# AudioMega_v102.net
KiCad netlist of a schematic drawn in EAGLE
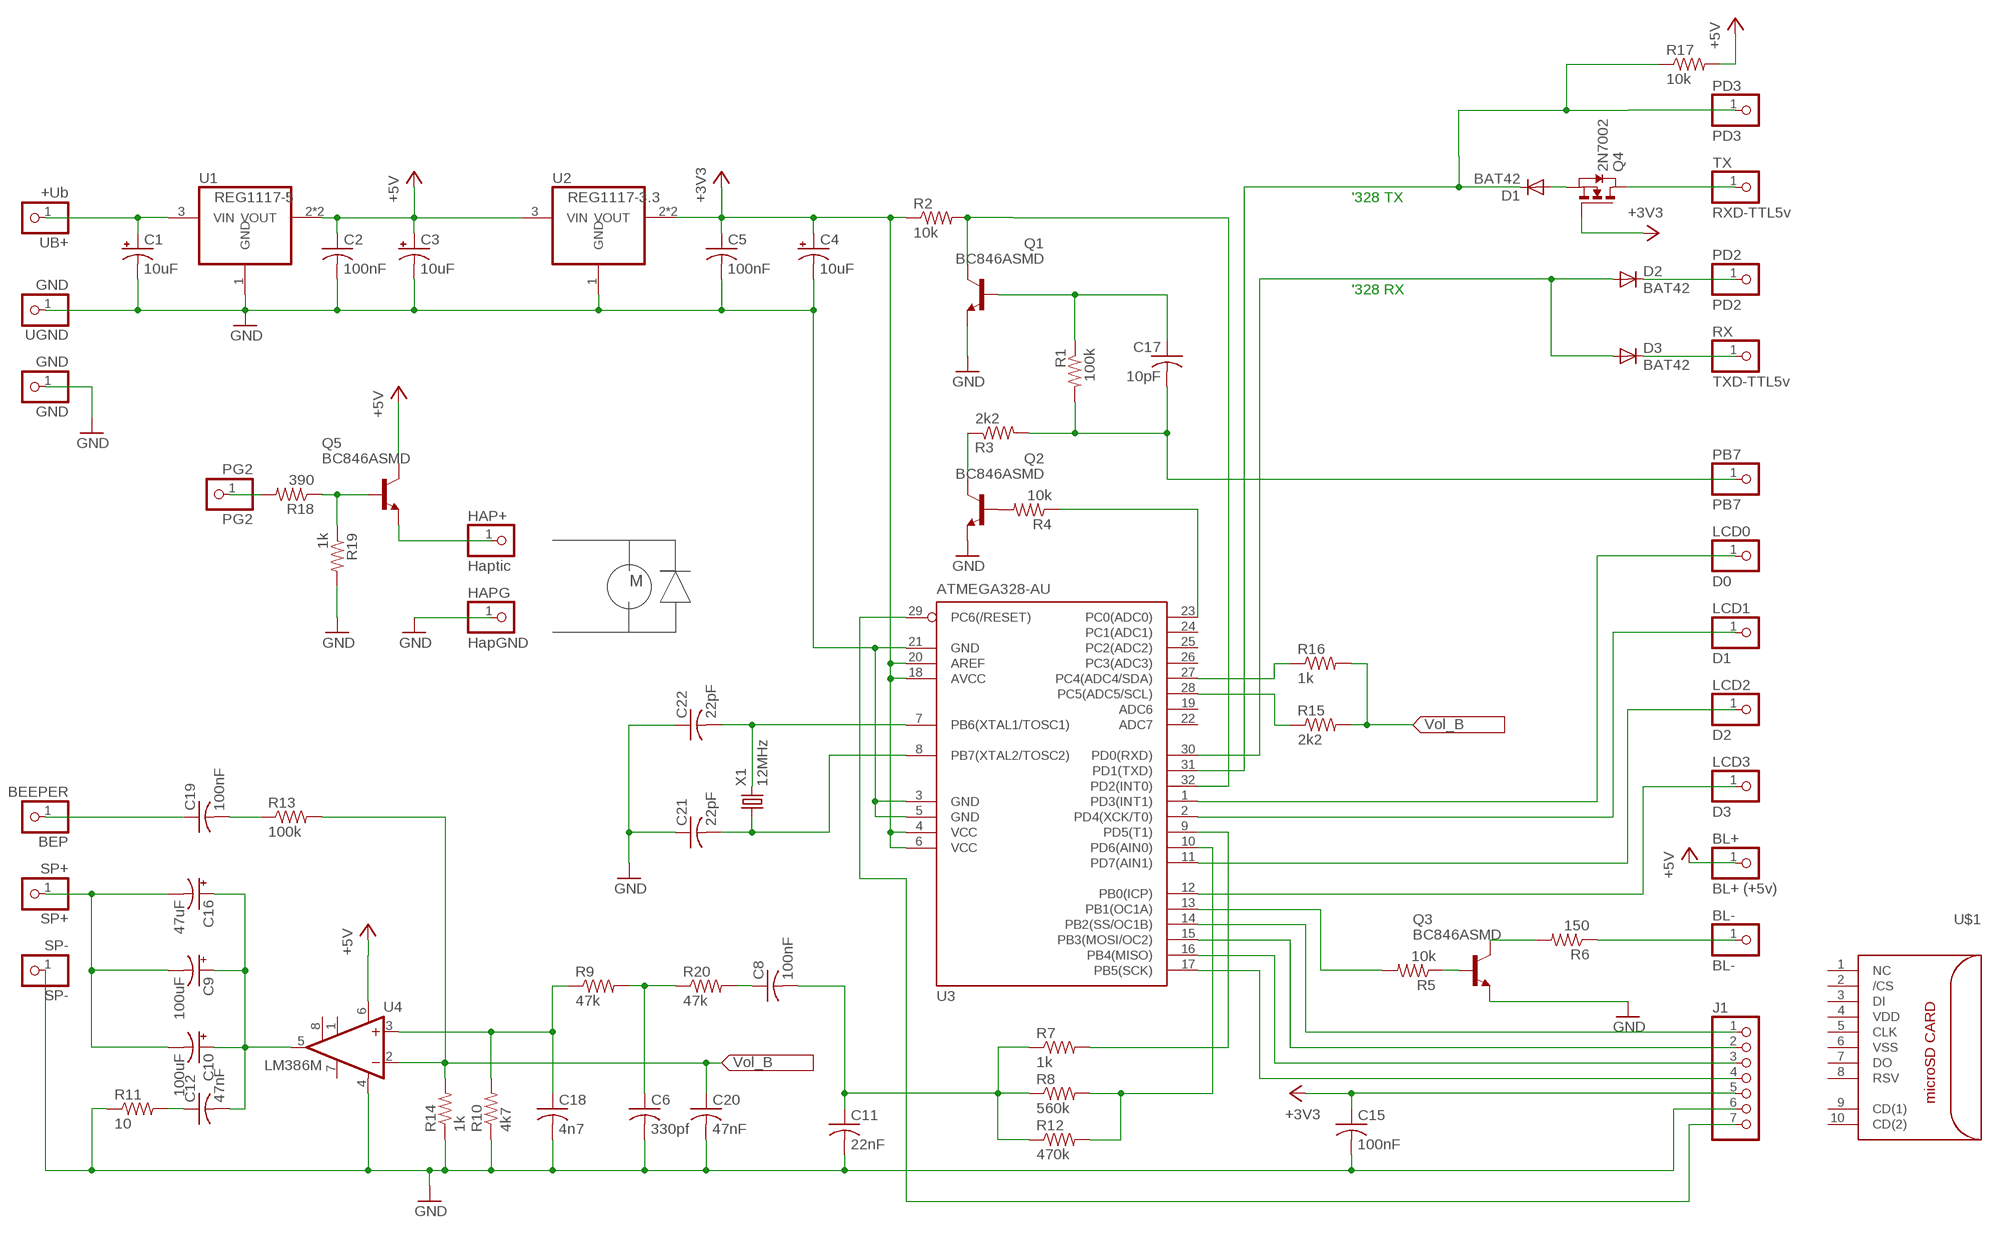
[diagram p0: schematic, sheet 1]

(export (version "E")
  (design (tool "Eeschema 10.0.6"))
  (components
    (comp (ref "BEP")
      (value "BEEPER")
      (footprint "eagle-import:1X01")
      (libsource (lib "eagle-import") (part "PINHD-1X1"))
    )
    (comp (ref "BL+")
      (value "BL+ (+5v)")
      (footprint "eagle-import:1X01")
      (libsource (lib "eagle-import") (part "PINHD-1X1"))
    )
    (comp (ref "BL-")
      (value "BL-")
      (footprint "eagle-import:1X01")
      (libsource (lib "eagle-import") (part "PINHD-1X1"))
    )
    (comp (ref "C1")
      (value "10uF")
      (footprint "eagle-import:CT3528")
      (libsource (lib "eagle-import") (part "CPOL-USCT3528"))
    )
    (comp (ref "C2")
      (value "100nF")
      (footprint "eagle-import:C1206")
      (libsource (lib "eagle-import") (part "C-USC1206"))
    )
    (comp (ref "C3")
      (value "10uF")
      (footprint "eagle-import:CT3528")
      (libsource (lib "eagle-import") (part "CPOL-USCT3528"))
    )
    (comp (ref "C4")
      (value "10uF")
      (footprint "eagle-import:CT3528")
      (libsource (lib "eagle-import") (part "CPOL-USCT3528"))
    )
    (comp (ref "C5")
      (value "100nF")
      (footprint "eagle-import:C1206")
      (libsource (lib "eagle-import") (part "C-USC1206"))
    )
    (comp (ref "C6")
      (value "330pf")
      (footprint "eagle-import:C1206")
      (libsource (lib "eagle-import") (part "C-USC1206"))
    )
    (comp (ref "C8")
      (value "100nF")
      (footprint "eagle-import:C1206")
      (libsource (lib "eagle-import") (part "C-USC1206"))
    )
    (comp (ref "C9")
      (value "100uF")
      (footprint "eagle-import:CT6032")
      (libsource (lib "eagle-import") (part "CPOL-USCT6032"))
    )
    (comp (ref "C10")
      (value "100uF")
      (footprint "eagle-import:CT6032")
      (libsource (lib "eagle-import") (part "CPOL-USCT6032"))
    )
    (comp (ref "C11")
      (value "22nF")
      (footprint "eagle-import:C1206")
      (libsource (lib "eagle-import") (part "C-USC1206"))
    )
    (comp (ref "C12")
      (value "47nF")
      (footprint "eagle-import:C1206")
      (libsource (lib "eagle-import") (part "C-USC1206"))
    )
    (comp (ref "C15")
      (value "100nF")
      (footprint "eagle-import:C1206")
      (libsource (lib "eagle-import") (part "C-USC1206"))
    )
    (comp (ref "C16")
      (value "47uF")
      (footprint "eagle-import:CT6032")
      (libsource (lib "eagle-import") (part "CPOL-USCT6032"))
    )
    (comp (ref "C17")
      (value "10pF")
      (footprint "eagle-import:C1206")
      (libsource (lib "eagle-import") (part "C-USC1206"))
    )
    (comp (ref "C18")
      (value "4n7")
      (footprint "eagle-import:C1206")
      (libsource (lib "eagle-import") (part "C-USC1206"))
    )
    (comp (ref "C19")
      (value "100nF")
      (footprint "eagle-import:C1206")
      (libsource (lib "eagle-import") (part "C-USC1206"))
    )
    (comp (ref "C20")
      (value "47nF")
      (footprint "eagle-import:C1206")
      (libsource (lib "eagle-import") (part "C-USC1206"))
    )
    (comp (ref "C21")
      (value "22pF")
      (footprint "eagle-import:C1206")
      (libsource (lib "eagle-import") (part "C-USC1206"))
    )
    (comp (ref "C22")
      (value "22pF")
      (footprint "eagle-import:C1206")
      (libsource (lib "eagle-import") (part "C-USC1206"))
    )
    (comp (ref "D1")
      (value "BAT42")
      (footprint "eagle-import:SOD123")
      (libsource (lib "eagle-import") (part "DIODE-SOD123"))
    )
    (comp (ref "D2")
      (value "BAT42")
      (footprint "eagle-import:SOD123")
      (libsource (lib "eagle-import") (part "DIODE-SOD123"))
    )
    (comp (ref "D3")
      (value "BAT42")
      (footprint "eagle-import:SOD123")
      (libsource (lib "eagle-import") (part "DIODE-SOD123"))
    )
    (comp (ref "GND")
      (value "GND")
      (footprint "eagle-import:1X01")
      (libsource (lib "eagle-import") (part "PINHD-1X1"))
    )
    (comp (ref "HAP+")
      (value "Haptic")
      (footprint "eagle-import:1X01")
      (libsource (lib "eagle-import") (part "PINHD-1X1"))
    )
    (comp (ref "HAPG")
      (value "HapGND")
      (footprint "eagle-import:1X01")
      (libsource (lib "eagle-import") (part "PINHD-1X1"))
    )
    (comp (ref "J1")
      (value "PINHD-1X7")
      (footprint "eagle-import:1X07")
      (libsource (lib "eagle-import") (part "PINHD-1X7"))
    )
    (comp (ref "LCD0")
      (value "D0")
      (footprint "eagle-import:1X01")
      (libsource (lib "eagle-import") (part "PINHD-1X1"))
    )
    (comp (ref "LCD1")
      (value "D1")
      (footprint "eagle-import:1X01")
      (libsource (lib "eagle-import") (part "PINHD-1X1"))
    )
    (comp (ref "LCD2")
      (value "D2")
      (footprint "eagle-import:1X01")
      (libsource (lib "eagle-import") (part "PINHD-1X1"))
    )
    (comp (ref "LCD3")
      (value "D3")
      (footprint "eagle-import:1X01")
      (libsource (lib "eagle-import") (part "PINHD-1X1"))
    )
    (comp (ref "PB7")
      (value "PB7")
      (footprint "eagle-import:1X01")
      (libsource (lib "eagle-import") (part "PINHD-1X1"))
    )
    (comp (ref "PD2")
      (value "PD2")
      (footprint "eagle-import:1X01")
      (libsource (lib "eagle-import") (part "PINHD-1X1"))
    )
    (comp (ref "PD3")
      (value "PD3")
      (footprint "eagle-import:1X01")
      (libsource (lib "eagle-import") (part "PINHD-1X1"))
    )
    (comp (ref "PG2")
      (value "PG2")
      (footprint "eagle-import:1X01")
      (libsource (lib "eagle-import") (part "PINHD-1X1"))
    )
    (comp (ref "Q1")
      (value "BC846ASMD")
      (footprint "eagle-import:SOT23")
      (libsource (lib "eagle-import") (part "BC846SMDA"))
    )
    (comp (ref "Q2")
      (value "BC846ASMD")
      (footprint "eagle-import:SOT23")
      (libsource (lib "eagle-import") (part "BC846SMDA"))
    )
    (comp (ref "Q3")
      (value "BC846ASMD")
      (footprint "eagle-import:SOT23")
      (libsource (lib "eagle-import") (part "BC846SMDA"))
    )
    (comp (ref "Q4")
      (value "2N7002")
      (footprint "eagle-import:SOT-23")
      (libsource (lib "eagle-import") (part "NMOSSOT23"))
    )
    (comp (ref "Q5")
      (value "BC846ASMD")
      (footprint "eagle-import:SOT23")
      (libsource (lib "eagle-import") (part "BC846SMDA"))
    )
    (comp (ref "R1")
      (value "100k")
      (footprint "eagle-import:R1206")
      (libsource (lib "eagle-import") (part "R-US_R1206"))
    )
    (comp (ref "R2")
      (value "10k")
      (footprint "eagle-import:R1206")
      (libsource (lib "eagle-import") (part "R-US_R1206"))
    )
    (comp (ref "R3")
      (value "2k2")
      (footprint "eagle-import:R1206")
      (libsource (lib "eagle-import") (part "R-US_R1206"))
    )
    (comp (ref "R4")
      (value "10k")
      (footprint "eagle-import:R1206")
      (libsource (lib "eagle-import") (part "R-US_R1206"))
    )
    (comp (ref "R5")
      (value "10k")
      (footprint "eagle-import:R1206")
      (libsource (lib "eagle-import") (part "R-US_R1206"))
    )
    (comp (ref "R6")
      (value "150")
      (footprint "eagle-import:R1206")
      (libsource (lib "eagle-import") (part "R-US_R1206"))
    )
    (comp (ref "R7")
      (value "1k")
      (footprint "eagle-import:R1206")
      (libsource (lib "eagle-import") (part "R-US_R1206"))
    )
    (comp (ref "R8")
      (value "560k")
      (footprint "eagle-import:R1206")
      (libsource (lib "eagle-import") (part "R-US_R1206"))
    )
    (comp (ref "R9")
      (value "47k")
      (footprint "eagle-import:R1206")
      (libsource (lib "eagle-import") (part "R-US_R1206"))
    )
    (comp (ref "R10")
      (value "4k7")
      (footprint "eagle-import:R1206")
      (libsource (lib "eagle-import") (part "R-US_R1206"))
    )
    (comp (ref "R11")
      (value "10")
      (footprint "eagle-import:R1206")
      (libsource (lib "eagle-import") (part "R-US_R1206"))
    )
    (comp (ref "R12")
      (value "470k")
      (footprint "eagle-import:R1206")
      (libsource (lib "eagle-import") (part "R-US_R1206"))
    )
    (comp (ref "R13")
      (value "100k")
      (footprint "eagle-import:R1206")
      (libsource (lib "eagle-import") (part "R-US_R1206"))
    )
    (comp (ref "R14")
      (value "1k")
      (footprint "eagle-import:R1206")
      (libsource (lib "eagle-import") (part "R-US_R1206"))
    )
    (comp (ref "R15")
      (value "2k2")
      (footprint "eagle-import:R1206")
      (libsource (lib "eagle-import") (part "R-US_R1206"))
    )
    (comp (ref "R16")
      (value "1k")
      (footprint "eagle-import:R1206")
      (libsource (lib "eagle-import") (part "R-US_R1206"))
    )
    (comp (ref "R17")
      (value "10k")
      (footprint "eagle-import:R1206")
      (libsource (lib "eagle-import") (part "R-US_R1206"))
    )
    (comp (ref "R18")
      (value "390")
      (footprint "eagle-import:R1206")
      (libsource (lib "eagle-import") (part "R-US_R1206"))
    )
    (comp (ref "R19")
      (value "1k")
      (footprint "eagle-import:R1206")
      (libsource (lib "eagle-import") (part "R-US_R1206"))
    )
    (comp (ref "R20")
      (value "47k")
      (footprint "eagle-import:R1206")
      (libsource (lib "eagle-import") (part "R-US_R1206"))
    )
    (comp (ref "RX")
      (value "TXD-TTL5v")
      (footprint "eagle-import:1X01")
      (libsource (lib "eagle-import") (part "PINHD-1X1"))
    )
    (comp (ref "SP+")
      (value "SP+")
      (footprint "eagle-import:1X01")
      (libsource (lib "eagle-import") (part "PINHD-1X1"))
    )
    (comp (ref "SP-")
      (value "SP-")
      (footprint "eagle-import:1X01")
      (libsource (lib "eagle-import") (part "PINHD-1X1"))
    )
    (comp (ref "TX")
      (value "RXD-TTL5v")
      (footprint "eagle-import:1X01")
      (libsource (lib "eagle-import") (part "PINHD-1X1"))
    )
    (comp (ref "U$1")
      (value "MICROSD_SPI_MODE")
      (footprint "eagle-import:MICRO_SD_CONNECTOR")
      (libsource (lib "eagle-import") (part "MICROSD_SPI_MODE"))
    )
    (comp (ref "U1")
      (value "REG1117-5")
      (footprint "eagle-import:SOT223")
      (fields (field (name "MPN") "REG1117"))
      (libsource (lib "eagle-import") (part "REG1117"))
    )
    (comp (ref "U2")
      (value "REG1117-3.3")
      (footprint "eagle-import:SOT223")
      (fields (field (name "MPN") "REG1117"))
      (libsource (lib "eagle-import") (part "REG1117"))
    )
    (comp (ref "U3")
      (value "ATMEGA328-AU")
      (footprint "eagle-import:TQFP32-08")
      (fields (field (name "MPN") "ATMEGA8-16AU"))
      (libsource (lib "eagle-import") (part "MEGA8-AI"))
    )
    (comp (ref "U4")
      (value "LM386M")
      (footprint "eagle-import:SO08")
      (libsource (lib "eagle-import") (part "LM386?-M1"))
    )
    (comp (ref "UB+")
      (value "+Ub")
      (footprint "eagle-import:1X01")
      (libsource (lib "eagle-import") (part "PINHD-1X1"))
    )
    (comp (ref "UGND")
      (value "GND")
      (footprint "eagle-import:1X01")
      (libsource (lib "eagle-import") (part "PINHD-1X1"))
    )
    (comp (ref "X1")
      (value "12MHz")
      (footprint "eagle-import:HC49UP")
      (libsource (lib "eagle-import") (part "CRYSTALHC49UP"))
    )
  )
  (nets
    (net (code "1") (name "+3V3") (class "Default")
      (node (ref "C15") (pin "1") (pinfunction "1_1") (pintype "passive"))
      (node (ref "C4") (pin "+") (pinfunction "+_+") (pintype "passive"))
      (node (ref "C5") (pin "1") (pinfunction "1_1") (pintype "passive"))
      (node (ref "J1") (pin "5") (pinfunction "5_5") (pintype "passive"))
      (node (ref "Q4") (pin "3") (pinfunction "G_3") (pintype "passive"))
      (node (ref "R2") (pin "1") (pinfunction "1_1") (pintype "passive"))
      (node (ref "U2") (pin "2") (pinfunction "VOUT_2") (pintype "output"))
      (node (ref "U2") (pin "4") (pinfunction "VOUT_4") (pintype "output"))
      (node (ref "U3") (pin "18") (pinfunction "AVCC_18") (pintype "power_in"))
      (node (ref "U3") (pin "20") (pinfunction "AREF_20") (pintype "passive"))
      (node (ref "U3") (pin "4") (pinfunction "VCC_4") (pintype "power_in"))
      (node (ref "U3") (pin "6") (pinfunction "VCC_6") (pintype "power_in"))
    )
    (net (code "2") (name "+5V") (class "Default")
      (node (ref "BL+") (pin "1") (pinfunction "1_1") (pintype "passive"))
      (node (ref "C2") (pin "1") (pinfunction "1_1") (pintype "passive"))
      (node (ref "C3") (pin "+") (pinfunction "+_+") (pintype "passive"))
      (node (ref "Q5") (pin "3") (pinfunction "C_3") (pintype "passive"))
      (node (ref "R17") (pin "2") (pinfunction "2_2") (pintype "passive"))
      (node (ref "U1") (pin "2") (pinfunction "VOUT_2") (pintype "output"))
      (node (ref "U1") (pin "4") (pinfunction "VOUT_4") (pintype "output"))
      (node (ref "U2") (pin "3") (pinfunction "VIN_3") (pintype "input"))
      (node (ref "U4") (pin "6") (pinfunction "VS_6") (pintype "power_in"))
    )
    (net (code "3") (name "/VOL_B") (class "Default")
      (node (ref "C20") (pin "1") (pinfunction "1_1") (pintype "passive"))
      (node (ref "R13") (pin "2") (pinfunction "2_2") (pintype "passive"))
      (node (ref "R14") (pin "2") (pinfunction "2_2") (pintype "passive"))
      (node (ref "R15") (pin "2") (pinfunction "2_2") (pintype "passive"))
      (node (ref "R16") (pin "2") (pinfunction "2_2") (pintype "passive"))
      (node (ref "U4") (pin "2") (pinfunction "-IN_2") (pintype "input"))
    )
    (net (code "4") (name "GND") (class "Default")
      (node (ref "C1") (pin "-") (pinfunction "-_-") (pintype "passive"))
      (node (ref "C11") (pin "2") (pinfunction "2_2") (pintype "passive"))
      (node (ref "C15") (pin "2") (pinfunction "2_2") (pintype "passive"))
      (node (ref "C18") (pin "2") (pinfunction "2_2") (pintype "passive"))
      (node (ref "C2") (pin "2") (pinfunction "2_2") (pintype "passive"))
      (node (ref "C20") (pin "2") (pinfunction "2_2") (pintype "passive"))
      (node (ref "C21") (pin "1") (pinfunction "1_1") (pintype "passive"))
      (node (ref "C22") (pin "1") (pinfunction "1_1") (pintype "passive"))
      (node (ref "C3") (pin "-") (pinfunction "-_-") (pintype "passive"))
      (node (ref "C4") (pin "-") (pinfunction "-_-") (pintype "passive"))
      (node (ref "C5") (pin "2") (pinfunction "2_2") (pintype "passive"))
      (node (ref "C6") (pin "2") (pinfunction "2_2") (pintype "passive"))
      (node (ref "GND") (pin "1") (pinfunction "1_1") (pintype "passive"))
      (node (ref "HAPG") (pin "1") (pinfunction "1_1") (pintype "passive"))
      (node (ref "J1") (pin "6") (pinfunction "6_6") (pintype "passive"))
      (node (ref "Q1") (pin "2") (pinfunction "E_2") (pintype "passive"))
      (node (ref "Q2") (pin "2") (pinfunction "E_2") (pintype "passive"))
      (node (ref "Q3") (pin "2") (pinfunction "E_2") (pintype "passive"))
      (node (ref "R10") (pin "1") (pinfunction "1_1") (pintype "passive"))
      (node (ref "R11") (pin "1") (pinfunction "1_1") (pintype "passive"))
      (node (ref "R14") (pin "1") (pinfunction "1_1") (pintype "passive"))
      (node (ref "R19") (pin "2") (pinfunction "2_2") (pintype "passive"))
      (node (ref "SP-") (pin "1") (pinfunction "1_1") (pintype "passive"))
      (node (ref "U1") (pin "1") (pinfunction "GND_1") (pintype "power_in"))
      (node (ref "U2") (pin "1") (pinfunction "GND_1") (pintype "power_in"))
      (node (ref "U3") (pin "21") (pinfunction "GND_21") (pintype "power_in"))
      (node (ref "U3") (pin "3") (pinfunction "GND_3") (pintype "power_in"))
      (node (ref "U3") (pin "5") (pinfunction "GND_5") (pintype "power_in"))
      (node (ref "U4") (pin "4") (pinfunction "GND_4") (pintype "power_in"))
      (node (ref "UGND") (pin "1") (pinfunction "1_1") (pintype "passive"))
    )
    (net (code "5") (name "Net-(BEP-Pad1)") (class "Default")
      (node (ref "BEP") (pin "1") (pinfunction "1_1") (pintype "passive"))
      (node (ref "C19") (pin "1") (pinfunction "1_1") (pintype "passive"))
    )
    (net (code "6") (name "Net-(BL--Pad1)") (class "Default")
      (node (ref "BL-") (pin "1") (pinfunction "1_1") (pintype "passive"))
      (node (ref "R6") (pin "1") (pinfunction "1_1") (pintype "passive"))
    )
    (net (code "7") (name "Net-(C6-Pad1)") (class "Default")
      (node (ref "C6") (pin "1") (pinfunction "1_1") (pintype "passive"))
      (node (ref "R20") (pin "1") (pinfunction "1_1") (pintype "passive"))
      (node (ref "R9") (pin "2") (pinfunction "2_2") (pintype "passive"))
    )
    (net (code "8") (name "Net-(C8-Pad1)") (class "Default")
      (node (ref "C8") (pin "1") (pinfunction "1_1") (pintype "passive"))
      (node (ref "R20") (pin "2") (pinfunction "2_2") (pintype "passive"))
    )
    (net (code "9") (name "Net-(C10-Pad-)") (class "Default")
      (node (ref "C10") (pin "-") (pinfunction "-_-") (pintype "passive"))
      (node (ref "C16") (pin "-") (pinfunction "-_-") (pintype "passive"))
      (node (ref "C9") (pin "-") (pinfunction "-_-") (pintype "passive"))
      (node (ref "SP+") (pin "1") (pinfunction "1_1") (pintype "passive"))
    )
    (net (code "10") (name "Net-(C11-Pad1)") (class "Default")
      (node (ref "C11") (pin "1") (pinfunction "1_1") (pintype "passive"))
      (node (ref "C8") (pin "2") (pinfunction "2_2") (pintype "passive"))
      (node (ref "R12") (pin "1") (pinfunction "1_1") (pintype "passive"))
      (node (ref "R7") (pin "1") (pinfunction "1_1") (pintype "passive"))
      (node (ref "R8") (pin "1") (pinfunction "1_1") (pintype "passive"))
    )
    (net (code "11") (name "Net-(C12-Pad1)") (class "Default")
      (node (ref "C12") (pin "1") (pinfunction "1_1") (pintype "passive"))
      (node (ref "R11") (pin "2") (pinfunction "2_2") (pintype "passive"))
    )
    (net (code "12") (name "Net-(C17-Pad2)") (class "Default")
      (node (ref "C17") (pin "2") (pinfunction "2_2") (pintype "passive"))
      (node (ref "PB7") (pin "1") (pinfunction "1_1") (pintype "passive"))
      (node (ref "R1") (pin "2") (pinfunction "2_2") (pintype "passive"))
      (node (ref "R3") (pin "2") (pinfunction "2_2") (pintype "passive"))
    )
    (net (code "13") (name "Net-(C19-Pad2)") (class "Default")
      (node (ref "C19") (pin "2") (pinfunction "2_2") (pintype "passive"))
      (node (ref "R13") (pin "1") (pinfunction "1_1") (pintype "passive"))
    )
    (net (code "14") (name "Net-(D2-PadC)") (class "Default")
      (node (ref "D2") (pin "C") (pinfunction "C_C") (pintype "passive"))
      (node (ref "PD2") (pin "1") (pinfunction "1_1") (pintype "passive"))
    )
    (net (code "15") (name "Net-(D3-PadC)") (class "Default")
      (node (ref "D3") (pin "C") (pinfunction "C_C") (pintype "passive"))
      (node (ref "RX") (pin "1") (pinfunction "1_1") (pintype "passive"))
    )
    (net (code "16") (name "Net-(PG2-Pad1)") (class "Default")
      (node (ref "PG2") (pin "1") (pinfunction "1_1") (pintype "passive"))
      (node (ref "R18") (pin "2") (pinfunction "2_2") (pintype "passive"))
    )
    (net (code "17") (name "Net-(Q1-B)") (class "Default")
      (node (ref "C17") (pin "1") (pinfunction "1_1") (pintype "passive"))
      (node (ref "Q1") (pin "1") (pinfunction "B_1") (pintype "passive"))
      (node (ref "R1") (pin "1") (pinfunction "1_1") (pintype "passive"))
    )
    (net (code "18") (name "Net-(Q1-C)") (class "Default")
      (node (ref "Q1") (pin "3") (pinfunction "C_3") (pintype "passive"))
      (node (ref "R2") (pin "2") (pinfunction "2_2") (pintype "passive"))
      (node (ref "U3") (pin "32") (pinfunction "PD2(INT0)_32") (pintype "bidirectional"))
    )
    (net (code "19") (name "Net-(Q2-B)") (class "Default")
      (node (ref "Q2") (pin "1") (pinfunction "B_1") (pintype "passive"))
      (node (ref "R4") (pin "2") (pinfunction "2_2") (pintype "passive"))
    )
    (net (code "20") (name "Net-(Q2-C)") (class "Default")
      (node (ref "Q2") (pin "3") (pinfunction "C_3") (pintype "passive"))
      (node (ref "R3") (pin "1") (pinfunction "1_1") (pintype "passive"))
    )
    (net (code "21") (name "Net-(Q3-B)") (class "Default")
      (node (ref "Q3") (pin "1") (pinfunction "B_1") (pintype "passive"))
      (node (ref "R5") (pin "1") (pinfunction "1_1") (pintype "passive"))
    )
    (net (code "22") (name "Net-(Q3-C)") (class "Default")
      (node (ref "Q3") (pin "3") (pinfunction "C_3") (pintype "passive"))
      (node (ref "R6") (pin "2") (pinfunction "2_2") (pintype "passive"))
    )
    (net (code "23") (name "Net-(Q4-D)") (class "Default")
      (node (ref "Q4") (pin "1") (pinfunction "D_1") (pintype "passive"))
      (node (ref "TX") (pin "1") (pinfunction "1_1") (pintype "passive"))
    )
    (net (code "24") (name "Net-(Q4-S)") (class "Default")
      (node (ref "D1") (pin "A") (pinfunction "A_A") (pintype "passive"))
      (node (ref "Q4") (pin "2") (pinfunction "S_2") (pintype "passive"))
    )
    (net (code "25") (name "Net-(Q5-B)") (class "Default")
      (node (ref "Q5") (pin "1") (pinfunction "B_1") (pintype "passive"))
      (node (ref "R18") (pin "1") (pinfunction "1_1") (pintype "passive"))
      (node (ref "R19") (pin "1") (pinfunction "1_1") (pintype "passive"))
    )
    (net (code "26") (name "Net-(Q5-E)") (class "Default")
      (node (ref "HAP+") (pin "1") (pinfunction "1_1") (pintype "passive"))
      (node (ref "Q5") (pin "2") (pinfunction "E_2") (pintype "passive"))
    )
    (net (code "27") (name "Net-(U1-VIN)") (class "Default")
      (node (ref "C1") (pin "+") (pinfunction "+_+") (pintype "passive"))
      (node (ref "U1") (pin "3") (pinfunction "VIN_3") (pintype "input"))
      (node (ref "UB+") (pin "1") (pinfunction "1_1") (pintype "passive"))
    )
    (net (code "28") (name "Net-(U3-PB0(ICP))") (class "Default")
      (node (ref "LCD3") (pin "1") (pinfunction "1_1") (pintype "passive"))
      (node (ref "U3") (pin "12") (pinfunction "PB0(ICP)_12") (pintype "bidirectional"))
    )
    (net (code "29") (name "Net-(U3-PB1(OC1A))") (class "Default")
      (node (ref "R5") (pin "2") (pinfunction "2_2") (pintype "passive"))
      (node (ref "U3") (pin "13") (pinfunction "PB1(OC1A)_13") (pintype "bidirectional"))
    )
    (net (code "30") (name "Net-(U3-PB2(SS{slash}OC1B))") (class "Default")
      (node (ref "J1") (pin "1") (pinfunction "1_1") (pintype "passive"))
      (node (ref "U3") (pin "14") (pinfunction "PB2(SS/OC1B)_14") (pintype "bidirectional"))
    )
    (net (code "31") (name "Net-(U3-PB3(MOSI{slash}OC2))") (class "Default")
      (node (ref "J1") (pin "2") (pinfunction "2_2") (pintype "passive"))
      (node (ref "U3") (pin "15") (pinfunction "PB3(MOSI/OC2)_15") (pintype "bidirectional"))
    )
    (net (code "32") (name "Net-(U3-PB4(MISO))") (class "Default")
      (node (ref "J1") (pin "3") (pinfunction "3_3") (pintype "passive"))
      (node (ref "U3") (pin "16") (pinfunction "PB4(MISO)_16") (pintype "bidirectional"))
    )
    (net (code "33") (name "Net-(U3-PB5(SCK))") (class "Default")
      (node (ref "J1") (pin "4") (pinfunction "4_4") (pintype "passive"))
      (node (ref "U3") (pin "17") (pinfunction "PB5(SCK)_17") (pintype "bidirectional"))
    )
    (net (code "34") (name "Net-(U3-PB6(XTAL1{slash}TOSC1))") (class "Default")
      (node (ref "C22") (pin "2") (pinfunction "2_2") (pintype "passive"))
      (node (ref "U3") (pin "7") (pinfunction "PB6(XTAL1/TOSC1)_7") (pintype "bidirectional"))
      (node (ref "X1") (pin "2") (pinfunction "2_2") (pintype "passive"))
    )
    (net (code "35") (name "Net-(U3-PB7(XTAL2{slash}TOSC2))") (class "Default")
      (node (ref "C21") (pin "2") (pinfunction "2_2") (pintype "passive"))
      (node (ref "U3") (pin "8") (pinfunction "PB7(XTAL2/TOSC2)_8") (pintype "bidirectional"))
      (node (ref "X1") (pin "1") (pinfunction "1_1") (pintype "passive"))
    )
    (net (code "36") (name "Net-(U3-PC0(ADC0))") (class "Default")
      (node (ref "R4") (pin "1") (pinfunction "1_1") (pintype "passive"))
      (node (ref "U3") (pin "23") (pinfunction "PC0(ADC0)_23") (pintype "bidirectional"))
    )
    (net (code "37") (name "Net-(U3-PC4(ADC4{slash}SDA))") (class "Default")
      (node (ref "R16") (pin "1") (pinfunction "1_1") (pintype "passive"))
      (node (ref "U3") (pin "27") (pinfunction "PC4(ADC4/SDA)_27") (pintype "bidirectional"))
    )
    (net (code "38") (name "Net-(U3-PC5(ADC5{slash}SCL))") (class "Default")
      (node (ref "R15") (pin "1") (pinfunction "1_1") (pintype "passive"))
      (node (ref "U3") (pin "28") (pinfunction "PC5(ADC5/SCL)_28") (pintype "bidirectional"))
    )
    (net (code "39") (name "Net-(U3-PC6({slash}RESET))") (class "Default")
      (node (ref "J1") (pin "7") (pinfunction "7_7") (pintype "passive"))
      (node (ref "U3") (pin "29") (pinfunction "PC6(/RESET)_29") (pintype "bidirectional"))
    )
    (net (code "40") (name "Net-(U3-PD0(RXD))") (class "Default")
      (node (ref "D2") (pin "A") (pinfunction "A_A") (pintype "passive"))
      (node (ref "D3") (pin "A") (pinfunction "A_A") (pintype "passive"))
      (node (ref "U3") (pin "30") (pinfunction "PD0(RXD)_30") (pintype "bidirectional"))
    )
    (net (code "41") (name "Net-(U3-PD1(TXD))") (class "Default")
      (node (ref "D1") (pin "C") (pinfunction "C_C") (pintype "passive"))
      (node (ref "PD3") (pin "1") (pinfunction "1_1") (pintype "passive"))
      (node (ref "R17") (pin "1") (pinfunction "1_1") (pintype "passive"))
      (node (ref "U3") (pin "31") (pinfunction "PD1(TXD)_31") (pintype "bidirectional"))
    )
    (net (code "42") (name "Net-(U3-PD3(INT1))") (class "Default")
      (node (ref "LCD0") (pin "1") (pinfunction "1_1") (pintype "passive"))
      (node (ref "U3") (pin "1") (pinfunction "PD3(INT1)_1") (pintype "bidirectional"))
    )
    (net (code "43") (name "Net-(U3-PD4(XCK{slash}T0))") (class "Default")
      (node (ref "LCD1") (pin "1") (pinfunction "1_1") (pintype "passive"))
      (node (ref "U3") (pin "2") (pinfunction "PD4(XCK/T0)_2") (pintype "bidirectional"))
    )
    (net (code "44") (name "Net-(U3-PD5(T1))") (class "Default")
      (node (ref "R7") (pin "2") (pinfunction "2_2") (pintype "passive"))
      (node (ref "U3") (pin "9") (pinfunction "PD5(T1)_9") (pintype "bidirectional"))
    )
    (net (code "45") (name "Net-(U3-PD6(AIN0))") (class "Default")
      (node (ref "R12") (pin "2") (pinfunction "2_2") (pintype "passive"))
      (node (ref "R8") (pin "2") (pinfunction "2_2") (pintype "passive"))
      (node (ref "U3") (pin "10") (pinfunction "PD6(AIN0)_10") (pintype "bidirectional"))
    )
    (net (code "46") (name "Net-(U3-PD7(AIN1))") (class "Default")
      (node (ref "LCD2") (pin "1") (pinfunction "1_1") (pintype "passive"))
      (node (ref "U3") (pin "11") (pinfunction "PD7(AIN1)_11") (pintype "bidirectional"))
    )
    (net (code "47") (name "Net-(U4-+IN)") (class "Default")
      (node (ref "C18") (pin "1") (pinfunction "1_1") (pintype "passive"))
      (node (ref "R10") (pin "2") (pinfunction "2_2") (pintype "passive"))
      (node (ref "R9") (pin "1") (pinfunction "1_1") (pintype "passive"))
      (node (ref "U4") (pin "3") (pinfunction "+IN_3") (pintype "input"))
    )
    (net (code "48") (name "Net-(U4-OUT)") (class "Default")
      (node (ref "C10") (pin "+") (pinfunction "+_+") (pintype "passive"))
      (node (ref "C12") (pin "2") (pinfunction "2_2") (pintype "passive"))
      (node (ref "C16") (pin "+") (pinfunction "+_+") (pintype "passive"))
      (node (ref "C9") (pin "+") (pinfunction "+_+") (pintype "passive"))
      (node (ref "U4") (pin "5") (pinfunction "OUT_5") (pintype "output"))
    )
    (net (code "49") (name "unconnected-(U$1-CD(1)-Pad9)") (class "Default")
      (node (ref "U$1") (pin "9") (pinfunction "CD(1)_9") (pintype "bidirectional"))
    )
    (net (code "50") (name "unconnected-(U$1-CD(2)-Pad10)") (class "Default")
      (node (ref "U$1") (pin "10") (pinfunction "CD(2)_10") (pintype "bidirectional"))
    )
    (net (code "51") (name "unconnected-(U$1-CLK-Pad5)") (class "Default")
      (node (ref "U$1") (pin "5") (pinfunction "CLK_5") (pintype "bidirectional"))
    )
    (net (code "52") (name "unconnected-(U$1-DI-Pad3)") (class "Default")
      (node (ref "U$1") (pin "3") (pinfunction "DI_3") (pintype "bidirectional"))
    )
    (net (code "53") (name "unconnected-(U$1-DO-Pad7)") (class "Default")
      (node (ref "U$1") (pin "7") (pinfunction "DO_7") (pintype "bidirectional"))
    )
    (net (code "54") (name "unconnected-(U$1-NC-Pad1)") (class "Default")
      (node (ref "U$1") (pin "1") (pinfunction "NC_1") (pintype "bidirectional"))
    )
    (net (code "55") (name "unconnected-(U$1-RSV-Pad8)") (class "Default")
      (node (ref "U$1") (pin "8") (pinfunction "RSV_8") (pintype "bidirectional"))
    )
    (net (code "56") (name "unconnected-(U$1-VDD-Pad4)") (class "Default")
      (node (ref "U$1") (pin "4") (pinfunction "VDD_4") (pintype "bidirectional"))
    )
    (net (code "57") (name "unconnected-(U$1-VSS-Pad6)") (class "Default")
      (node (ref "U$1") (pin "6") (pinfunction "VSS_6") (pintype "bidirectional"))
    )
    (net (code "58") (name "unconnected-(U$1-{slash}CS-Pad2)") (class "Default")
      (node (ref "U$1") (pin "2") (pinfunction "/CS_2") (pintype "bidirectional"))
    )
    (net (code "59") (name "unconnected-(U3-ADC6-Pad19)") (class "Default")
      (node (ref "U3") (pin "19") (pinfunction "ADC6_19") (pintype "bidirectional"))
    )
    (net (code "60") (name "unconnected-(U3-ADC7-Pad22)") (class "Default")
      (node (ref "U3") (pin "22") (pinfunction "ADC7_22") (pintype "bidirectional"))
    )
    (net (code "61") (name "unconnected-(U3-PC1(ADC1)-Pad24)") (class "Default")
      (node (ref "U3") (pin "24") (pinfunction "PC1(ADC1)_24") (pintype "bidirectional"))
    )
    (net (code "62") (name "unconnected-(U3-PC2(ADC2)-Pad25)") (class "Default")
      (node (ref "U3") (pin "25") (pinfunction "PC2(ADC2)_25") (pintype "bidirectional"))
    )
    (net (code "63") (name "unconnected-(U3-PC3(ADC3)-Pad26)") (class "Default")
      (node (ref "U3") (pin "26") (pinfunction "PC3(ADC3)_26") (pintype "bidirectional"))
    )
    (net (code "64") (name "unconnected-(U4-BYPASS-Pad7)") (class "Default")
      (node (ref "U4") (pin "7") (pinfunction "BYPASS_7") (pintype "passive"))
    )
    (net (code "65") (name "unconnected-(U4-GAIN-Pad1)") (class "Default")
      (node (ref "U4") (pin "1") (pinfunction "GAIN_1") (pintype "passive"))
    )
    (net (code "66") (name "unconnected-(U4-GAIN-Pad8)") (class "Default")
      (node (ref "U4") (pin "8") (pinfunction "GAIN_8") (pintype "passive"))
    )
  )
)
